# rigidPCB.net
KiCad netlist of a schematic drawn in Altium Designer
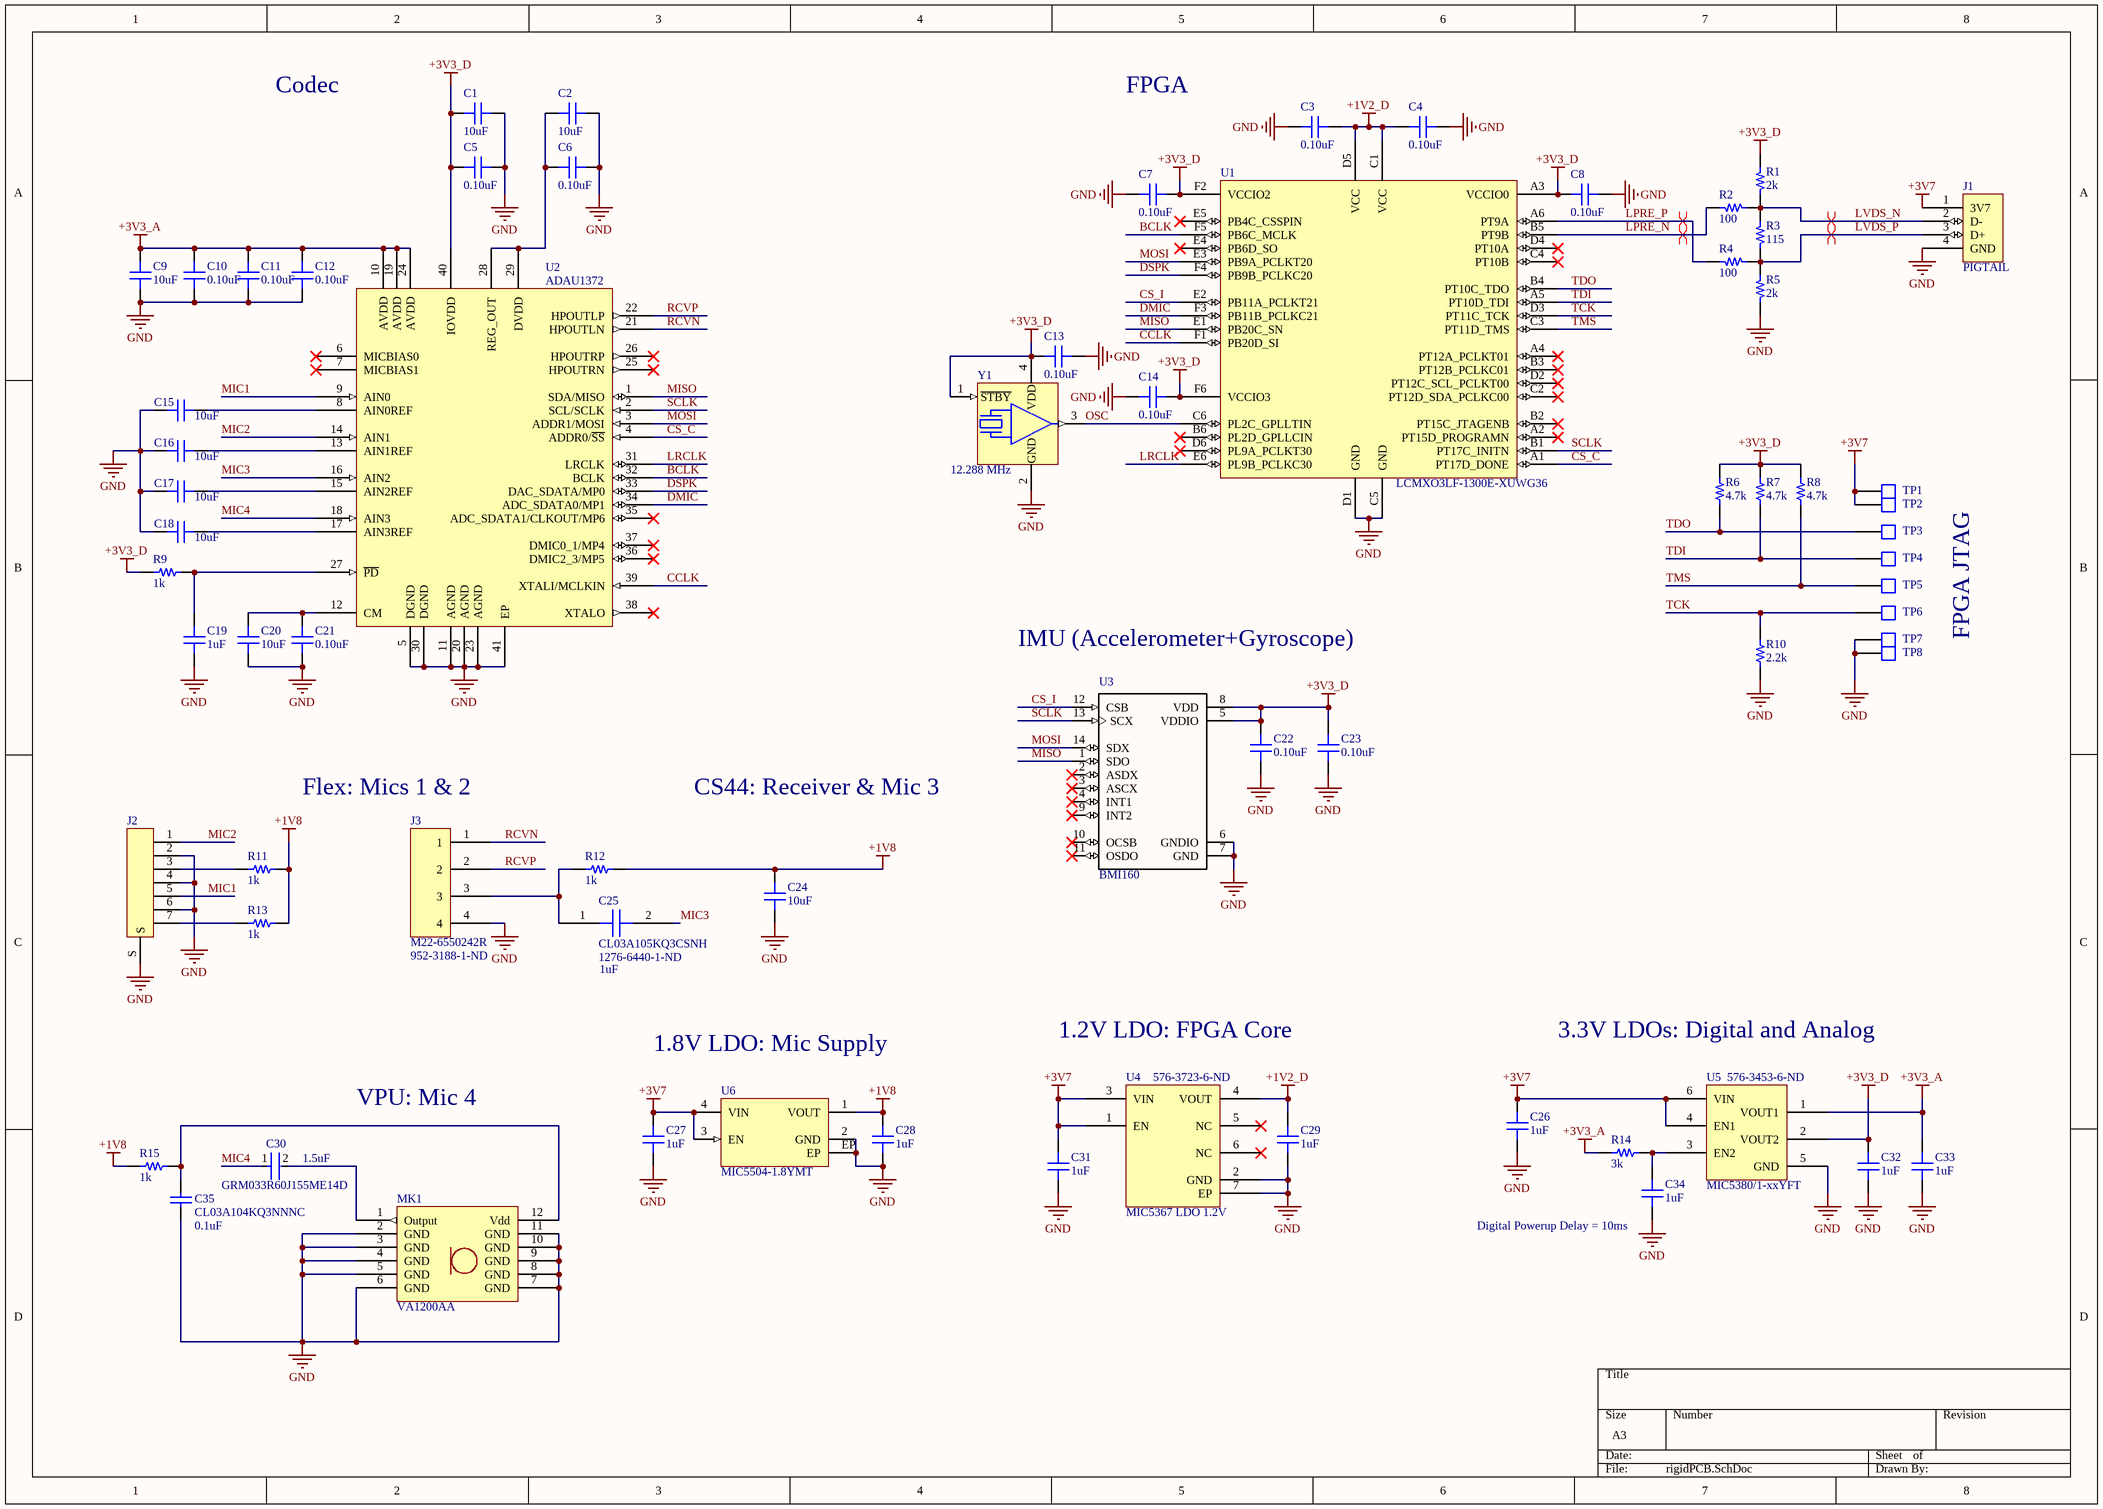
[diagram p0: rigidPCB.SchDoc]

(export (version "E")
  (design (tool "Eeschema 10.0.6"))
  (components
    (comp (ref "C1")
      (value "10uF")
      (footprint "CAP 0402/1005")
      (description "CAP CER 10UF 6.3V X5R 0402")
      (fields
        (field (name "PART NUMBER") "C1005X5R0J106M050BC")
        (field (name "MANUFACTURER") "TDK Corporation")
      )
      (libsource (lib "Celestial Library Database") (part "Capacitor"))
    )
    (comp (ref "C2")
      (value "10uF")
      (footprint "CAP 0402/1005")
      (description "CAP CER 10UF 6.3V X5R 0402")
      (fields
        (field (name "PART NUMBER") "C1005X5R0J106M050BC")
        (field (name "MANUFACTURER") "TDK Corporation")
      )
      (libsource (lib "Celestial Library Database") (part "Capacitor"))
    )
    (comp (ref "C3")
      (value "0.10uF")
      (footprint "CAP 0201/0603")
      (description "CAP CER 0.1UF 10V X5R 0201")
      (fields
        (field (name "PART NUMBER") "CL03A104KP3NNNC")
        (field (name "MANUFACTURER") "Samsung Electro-Mechanics America, Inc.")
      )
      (libsource (lib "Celestial Library Database") (part "Capacitor"))
    )
    (comp (ref "C4")
      (value "0.10uF")
      (footprint "CAP 0201/0603")
      (description "CAP CER 0.1UF 10V X5R 0201")
      (fields
        (field (name "PART NUMBER") "CL03A104KP3NNNC")
        (field (name "MANUFACTURER") "Samsung Electro-Mechanics America, Inc.")
      )
      (libsource (lib "Celestial Library Database") (part "Capacitor"))
    )
    (comp (ref "C5")
      (value "0.10uF")
      (footprint "CAP 0201/0603")
      (description "CAP CER 0.1UF 10V X5R 0201")
      (fields
        (field (name "PART NUMBER") "CL03A104KP3NNNC")
        (field (name "MANUFACTURER") "Samsung Electro-Mechanics America, Inc.")
      )
      (libsource (lib "Celestial Library Database") (part "Capacitor"))
    )
    (comp (ref "C6")
      (value "0.10uF")
      (footprint "CAP 0201/0603")
      (description "CAP CER 0.1UF 10V X5R 0201")
      (fields
        (field (name "PART NUMBER") "CL03A104KP3NNNC")
        (field (name "MANUFACTURER") "Samsung Electro-Mechanics America, Inc.")
      )
      (libsource (lib "Celestial Library Database") (part "Capacitor"))
    )
    (comp (ref "C7")
      (value "0.10uF")
      (footprint "CAP 0201/0603")
      (description "CAP CER 0.1UF 10V X5R 0201")
      (fields
        (field (name "PART NUMBER") "CL03A104KP3NNNC")
        (field (name "MANUFACTURER") "Samsung Electro-Mechanics America, Inc.")
      )
      (libsource (lib "Celestial Library Database") (part "Capacitor"))
    )
    (comp (ref "C8")
      (value "0.10uF")
      (footprint "CAP 0201/0603")
      (description "CAP CER 0.1UF 10V X5R 0201")
      (fields
        (field (name "PART NUMBER") "CL03A104KP3NNNC")
        (field (name "MANUFACTURER") "Samsung Electro-Mechanics America, Inc.")
      )
      (libsource (lib "Celestial Library Database") (part "Capacitor"))
    )
    (comp (ref "C9")
      (value "10uF")
      (footprint "CAP 0402/1005")
      (description "CAP CER 10UF 6.3V X5R 0402")
      (fields
        (field (name "PART NUMBER") "C1005X5R0J106M050BC")
        (field (name "MANUFACTURER") "TDK Corporation")
      )
      (libsource (lib "Celestial Library Database") (part "Capacitor"))
    )
    (comp (ref "C10")
      (value "0.10uF")
      (footprint "CAP 0201/0603")
      (description "CAP CER 0.1UF 10V X5R 0201")
      (fields
        (field (name "PART NUMBER") "CL03A104KP3NNNC")
        (field (name "MANUFACTURER") "Samsung Electro-Mechanics America, Inc.")
      )
      (libsource (lib "Celestial Library Database") (part "Capacitor"))
    )
    (comp (ref "C11")
      (value "0.10uF")
      (footprint "CAP 0201/0603")
      (description "CAP CER 0.1UF 10V X5R 0201")
      (fields
        (field (name "PART NUMBER") "CL03A104KP3NNNC")
        (field (name "MANUFACTURER") "Samsung Electro-Mechanics America, Inc.")
      )
      (libsource (lib "Celestial Library Database") (part "Capacitor"))
    )
    (comp (ref "C12")
      (value "0.10uF")
      (footprint "CAP 0201/0603")
      (description "CAP CER 0.1UF 10V X5R 0201")
      (fields
        (field (name "PART NUMBER") "CL03A104KP3NNNC")
        (field (name "MANUFACTURER") "Samsung Electro-Mechanics America, Inc.")
      )
      (libsource (lib "Celestial Library Database") (part "Capacitor"))
    )
    (comp (ref "C13")
      (value "0.10uF")
      (footprint "CAP 0201/0603")
      (description "CAP CER 0.1UF 10V X5R 0201")
      (fields
        (field (name "PART NUMBER") "CL03A104KP3NNNC")
        (field (name "MANUFACTURER") "Samsung Electro-Mechanics America, Inc.")
      )
      (libsource (lib "Celestial Library Database") (part "Capacitor"))
    )
    (comp (ref "C14")
      (value "0.10uF")
      (footprint "CAP 0201/0603")
      (description "CAP CER 0.1UF 10V X5R 0201")
      (fields
        (field (name "PART NUMBER") "CL03A104KP3NNNC")
        (field (name "MANUFACTURER") "Samsung Electro-Mechanics America, Inc.")
      )
      (libsource (lib "Celestial Library Database") (part "Capacitor"))
    )
    (comp (ref "C15")
      (value "10uF")
      (footprint "CAP 0402/1005")
      (description "CAP CER 10UF 6.3V X5R 0402")
      (fields
        (field (name "PART NUMBER") "C1005X5R0J106M050BC")
        (field (name "MANUFACTURER") "TDK Corporation")
      )
      (libsource (lib "Celestial Library Database") (part "Capacitor"))
    )
    (comp (ref "C16")
      (value "10uF")
      (footprint "CAP 0402/1005")
      (description "CAP CER 10UF 6.3V X5R 0402")
      (fields
        (field (name "PART NUMBER") "C1005X5R0J106M050BC")
        (field (name "MANUFACTURER") "TDK Corporation")
      )
      (libsource (lib "Celestial Library Database") (part "Capacitor"))
    )
    (comp (ref "C17")
      (value "10uF")
      (footprint "CAP 0402/1005")
      (description "CAP CER 10UF 6.3V X5R 0402")
      (fields
        (field (name "PART NUMBER") "C1005X5R0J106M050BC")
        (field (name "MANUFACTURER") "TDK Corporation")
      )
      (libsource (lib "Celestial Library Database") (part "Capacitor"))
    )
    (comp (ref "C18")
      (value "10uF")
      (footprint "CAP 0402/1005")
      (description "CAP CER 10UF 6.3V X5R 0402")
      (fields
        (field (name "PART NUMBER") "C1005X5R0J106M050BC")
        (field (name "MANUFACTURER") "TDK Corporation")
      )
      (libsource (lib "Celestial Library Database") (part "Capacitor"))
    )
    (comp (ref "C19")
      (value "1uF")
      (footprint "CAP 0201/0603")
      (description "CAP CER 1UF 6.3V X5R 0201")
      (fields (field (name "PART NUMBER") "02016D105MAT2A") (field (name "MANUFACTURER") "AVX Corporation"))
      (libsource (lib "Celestial Library Database") (part "Capacitor"))
    )
    (comp (ref "C20")
      (value "10uF")
      (footprint "CAP 0402/1005")
      (description "CAP CER 10UF 6.3V X5R 0402")
      (fields
        (field (name "PART NUMBER") "C1005X5R0J106M050BC")
        (field (name "MANUFACTURER") "TDK Corporation")
      )
      (libsource (lib "Celestial Library Database") (part "Capacitor"))
    )
    (comp (ref "C21")
      (value "0.10uF")
      (footprint "CAP 0201/0603")
      (description "CAP CER 0.1UF 10V X5R 0201")
      (fields
        (field (name "PART NUMBER") "CL03A104KP3NNNC")
        (field (name "MANUFACTURER") "Samsung Electro-Mechanics America, Inc.")
      )
      (libsource (lib "Celestial Library Database") (part "Capacitor"))
    )
    (comp (ref "C22")
      (value "0.10uF")
      (footprint "CAP 0201/0603")
      (description "CAP CER 0.1UF 10V X5R 0201")
      (fields
        (field (name "PART NUMBER") "CL03A104KP3NNNC")
        (field (name "MANUFACTURER") "Samsung Electro-Mechanics America, Inc.")
      )
      (libsource (lib "Celestial Library Database") (part "Capacitor"))
    )
    (comp (ref "C23")
      (value "0.10uF")
      (footprint "CAP 0201/0603")
      (description "CAP CER 0.1UF 10V X5R 0201")
      (fields
        (field (name "PART NUMBER") "CL03A104KP3NNNC")
        (field (name "MANUFACTURER") "Samsung Electro-Mechanics America, Inc.")
      )
      (libsource (lib "Celestial Library Database") (part "Capacitor"))
    )
    (comp (ref "C24")
      (value "10uF")
      (footprint "CAP 0402/1005")
      (description "CAP CER 10UF 6.3V X5R 0402")
      (fields
        (field (name "PART NUMBER") "C1005X5R0J106M050BC")
        (field (name "MANUFACTURER") "TDK Corporation")
      )
      (libsource (lib "Celestial Library Database") (part "Capacitor"))
    )
    (comp (ref "C25")
      (value "CL03A105KQ3CSNH")
      (footprint "CL03A105KQ3CSNH")
      (description "1 µF ±10% 6.3V Ceramic Capacitor X5R 0201 (0603 Metric)")
      (fields (field (name "SUPPLIER PART NUMBER 1") "1276-6440-1-ND"))
      (libsource (lib "OSP_DJB_Rigid") (part "CL03A105KQ3CSNH"))
    )
    (comp (ref "C26")
      (value "1uF")
      (footprint "CAP 0201/0603")
      (description "CAP CER 1UF 6.3V X5R 0201")
      (fields (field (name "PART NUMBER") "02016D105MAT2A") (field (name "MANUFACTURER") "AVX Corporation"))
      (libsource (lib "Celestial Library Database") (part "Capacitor"))
    )
    (comp (ref "C27")
      (value "1uF")
      (footprint "CAP 0201/0603")
      (description "CAP CER 1UF 6.3V X5R 0201")
      (fields (field (name "PART NUMBER") "02016D105MAT2A") (field (name "MANUFACTURER") "AVX Corporation"))
      (libsource (lib "Celestial Library Database") (part "Capacitor"))
    )
    (comp (ref "C28")
      (value "1uF")
      (footprint "CAP 0201/0603")
      (description "CAP CER 1UF 6.3V X5R 0201")
      (fields (field (name "PART NUMBER") "02016D105MAT2A") (field (name "MANUFACTURER") "AVX Corporation"))
      (libsource (lib "Celestial Library Database") (part "Capacitor"))
    )
    (comp (ref "C29")
      (value "1uF")
      (footprint "CAP 0201/0603")
      (description "CAP CER 1UF 6.3V X5R 0201")
      (fields (field (name "PART NUMBER") "02016D105MAT2A") (field (name "MANUFACTURER") "AVX Corporation"))
      (libsource (lib "Celestial Library Database") (part "Capacitor"))
    )
    (comp (ref "C30")
      (value "GRM033R60J155ME14D")
      (footprint "FP-GRM033-0_03-IPC_B")
      (description "Chip Multilayer Ceramic Capacitors for General Purpose, 0201, 1.5uF, X5R, 15%, 20%, 6.3V")
      (fields (field (name "TOLERANCE") "20%"))
      (libsource (lib "Altium Content Vault") (part "b4654b650e69147ec39a6b967a45e02"))
    )
    (comp (ref "C31")
      (value "1uF")
      (footprint "CAP 0201/0603")
      (description "CAP CER 1UF 6.3V X5R 0201")
      (fields (field (name "PART NUMBER") "02016D105MAT2A") (field (name "MANUFACTURER") "AVX Corporation"))
      (libsource (lib "Celestial Library Database") (part "Capacitor"))
    )
    (comp (ref "C32")
      (value "1uF")
      (footprint "CAP 0201/0603")
      (description "CAP CER 1UF 6.3V X5R 0201")
      (fields (field (name "PART NUMBER") "02016D105MAT2A") (field (name "MANUFACTURER") "AVX Corporation"))
      (libsource (lib "Celestial Library Database") (part "Capacitor"))
    )
    (comp (ref "C33")
      (value "1uF")
      (footprint "CAP 0201/0603")
      (description "CAP CER 1UF 6.3V X5R 0201")
      (fields (field (name "PART NUMBER") "02016D105MAT2A") (field (name "MANUFACTURER") "AVX Corporation"))
      (libsource (lib "Celestial Library Database") (part "Capacitor"))
    )
    (comp (ref "C34")
      (value "1uF")
      (footprint "CAP 0201/0603")
      (description "CAP CER 1UF 6.3V X5R 0201")
      (fields (field (name "PART NUMBER") "02016D105MAT2A") (field (name "MANUFACTURER") "AVX Corporation"))
      (libsource (lib "Celestial Library Database") (part "Capacitor"))
    )
    (comp (ref "C35")
      (value "CL03A104KQ3NNNC")
      (footprint "CAPC0603X33X15ML03T05")
      (fields (field (name "MANUFACTURER") "Samsung"))
      (libsource (lib "Altium Content Vault") (part "CAP"))
    )
    (comp (ref "J1")
      (value "PIGTAIL")
      (footprint "PIGTAIL")
      (libsource (lib "Mark_Library1") (part "PIGTAIL"))
    )
    (comp (ref "J2")
      (value "FFC")
      (footprint "HIROSE_FH58M-7S-0.25SHW-99")
      (description "Hirose FH58M-7S-0.25SHW(99) 7-pin Top+Bottom Contact FFC Connector")
      (libsource (lib "OSP_Symbols") (part "HIROSE_FH58M-7S-0.25SHW-99"))
    )
    (comp (ref "J3")
      (value "M22-6550242R")
      (footprint "M22-6550242R")
      (description "4 Position Receptacle Connector 0.079\" (2.00mm) Surface Mount, Right Angle Gold")
      (fields (field (name "SUPPLIER PART NUMBER 1") "952-3188-1-ND"))
      (libsource (lib "OSP_DJB_Rigid") (part "M22-6550242R"))
    )
    (comp (ref "MK1")
      (value "VA1200AA")
      (footprint "VA1200AA")
      (description "Bone Conductor Sensor Accelerometer")
      (libsource (lib "OSP_DJB_Rigid") (part "VA1200AA"))
    )
    (comp (ref "R1")
      (value "2k")
      (footprint "RES 0201/0603")
      (description "RES SMD 2K OHM 1% 1/20W 0201")
      (fields (field (name "PART NUMBER") "RC0201FR-072KL") (field (name "MANUFACTURER") "Yageo"))
      (libsource (lib "Celestial Library Database") (part "Resistor"))
    )
    (comp (ref "R2")
      (value "100")
      (footprint "RES 0201/0603")
      (description "RES SMD 100 OHM 1% 1/20W 0201")
      (fields
        (field (name "PART NUMBER") "RC0603F101CS")
        (field (name "MANUFACTURER") "Samsung Electro-Mechanics America, Inc.")
      )
      (libsource (lib "Celestial Library Database") (part "Resistor"))
    )
    (comp (ref "R3")
      (value "115")
      (footprint "RES 0201/0603")
      (description "RES SMD 115 OHM 1% 1/20W 0201")
      (fields (field (name "PART NUMBER") "RC0201FR-07115RL") (field (name "MANUFACTURER") "Yageo"))
      (libsource (lib "Celestial Library Database") (part "Resistor"))
    )
    (comp (ref "R4")
      (value "100")
      (footprint "RES 0201/0603")
      (description "RES SMD 100 OHM 1% 1/20W 0201")
      (fields
        (field (name "PART NUMBER") "RC0603F101CS")
        (field (name "MANUFACTURER") "Samsung Electro-Mechanics America, Inc.")
      )
      (libsource (lib "Celestial Library Database") (part "Resistor"))
    )
    (comp (ref "R5")
      (value "2k")
      (footprint "RES 0201/0603")
      (description "RES SMD 2K OHM 1% 1/20W 0201")
      (fields (field (name "PART NUMBER") "RC0201FR-072KL") (field (name "MANUFACTURER") "Yageo"))
      (libsource (lib "Celestial Library Database") (part "Resistor"))
    )
    (comp (ref "R6")
      (value "4.7k")
      (footprint "RES 0201/0603")
      (description "RES SMD 4.7K OHM 1% 1/20W 0201")
      (fields (field (name "PART NUMBER") "RC0201FR-074K7L") (field (name "MANUFACTURER") "Yageo"))
      (libsource (lib "Celestial Library Database") (part "Resistor"))
    )
    (comp (ref "R7")
      (value "4.7k")
      (footprint "RES 0201/0603")
      (description "RES SMD 4.7K OHM 1% 1/20W 0201")
      (fields (field (name "PART NUMBER") "RC0201FR-074K7L") (field (name "MANUFACTURER") "Yageo"))
      (libsource (lib "Celestial Library Database") (part "Resistor"))
    )
    (comp (ref "R8")
      (value "4.7k")
      (footprint "RES 0201/0603")
      (description "RES SMD 4.7K OHM 1% 1/20W 0201")
      (fields (field (name "PART NUMBER") "RC0201FR-074K7L") (field (name "MANUFACTURER") "Yageo"))
      (libsource (lib "Celestial Library Database") (part "Resistor"))
    )
    (comp (ref "R9")
      (value "1k")
      (footprint "RES 0201/0603")
      (description "RES SMD 1K OHM 5% 1/20W 0201")
      (fields (field (name "PART NUMBER") "RC0201JR-071KL") (field (name "MANUFACTURER") "Yageo"))
      (libsource (lib "Celestial Library Database") (part "Resistor"))
    )
    (comp (ref "R10")
      (value "2.2k")
      (footprint "RES 0201/0603")
      (description "RES SMD 2.2K OHM 1% 1/20W 0201")
      (fields
        (field (name "PART NUMBER") "RC0603F222CS")
        (field (name "MANUFACTURER") "Samsung Electro-Mechanics America, Inc.")
      )
      (libsource (lib "Celestial Library Database") (part "Resistor"))
    )
    (comp (ref "R11")
      (value "1k")
      (footprint "RES 0201/0603")
      (description "RES SMD 1K OHM 5% 1/20W 0201")
      (fields (field (name "PART NUMBER") "RC0201JR-071KL") (field (name "MANUFACTURER") "Yageo"))
      (libsource (lib "Celestial Library Database") (part "Resistor"))
    )
    (comp (ref "R12")
      (value "1k")
      (footprint "RES 0201/0603")
      (description "RES SMD 1K OHM 5% 1/20W 0201")
      (fields (field (name "PART NUMBER") "RC0201JR-071KL") (field (name "MANUFACTURER") "Yageo"))
      (libsource (lib "Celestial Library Database") (part "Resistor"))
    )
    (comp (ref "R13")
      (value "1k")
      (footprint "RES 0201/0603")
      (description "RES SMD 1K OHM 5% 1/20W 0201")
      (fields (field (name "PART NUMBER") "RC0201JR-071KL") (field (name "MANUFACTURER") "Yageo"))
      (libsource (lib "Celestial Library Database") (part "Resistor"))
    )
    (comp (ref "R14")
      (value "3k")
      (footprint "RES 0201/0603")
      (description "RES SMD 3K OHM 1% 1/20W 0201")
      (fields (field (name "PART NUMBER") "RC0201FR-073KL") (field (name "MANUFACTURER") "Yageo"))
      (libsource (lib "Celestial Library Database") (part "Resistor"))
    )
    (comp (ref "R15")
      (value "1k")
      (footprint "RES 0201/0603")
      (description "RES SMD 1K OHM 5% 1/20W 0201")
      (fields (field (name "PART NUMBER") "RC0201JR-071KL") (field (name "MANUFACTURER") "Yageo"))
      (libsource (lib "Celestial Library Database") (part "Resistor"))
    )
    (comp (ref "TP1")
      (value "TP_SMD_DJB")
      (footprint "TP_SMD_DJB")
      (description "Digital Jellybean Style SMD Test Point")
      (libsource (lib "OSP_Symbols") (part "TP_SMD_DJB"))
    )
    (comp (ref "TP2")
      (value "TP_SMD_DJB")
      (footprint "TP_SMD_DJB")
      (description "Digital Jellybean Style SMD Test Point")
      (libsource (lib "OSP_Symbols") (part "TP_SMD_DJB"))
    )
    (comp (ref "TP3")
      (value "TP_SMD_DJB")
      (footprint "TP_SMD_DJB")
      (description "Digital Jellybean Style SMD Test Point")
      (libsource (lib "OSP_Symbols") (part "TP_SMD_DJB"))
    )
    (comp (ref "TP4")
      (value "TP_SMD_DJB")
      (footprint "TP_SMD_DJB")
      (description "Digital Jellybean Style SMD Test Point")
      (libsource (lib "OSP_Symbols") (part "TP_SMD_DJB"))
    )
    (comp (ref "TP5")
      (value "TP_SMD_DJB")
      (footprint "TP_SMD_DJB")
      (description "Digital Jellybean Style SMD Test Point")
      (libsource (lib "OSP_Symbols") (part "TP_SMD_DJB"))
    )
    (comp (ref "TP6")
      (value "TP_SMD_DJB")
      (footprint "TP_SMD_DJB")
      (description "Digital Jellybean Style SMD Test Point")
      (libsource (lib "OSP_Symbols") (part "TP_SMD_DJB"))
    )
    (comp (ref "TP7")
      (value "TP_SMD_DJB")
      (footprint "TP_SMD_DJB")
      (description "Digital Jellybean Style SMD Test Point")
      (libsource (lib "OSP_Symbols") (part "TP_SMD_DJB"))
    )
    (comp (ref "TP8")
      (value "TP_SMD_DJB")
      (footprint "TP_SMD_DJB")
      (description "Digital Jellybean Style SMD Test Point")
      (libsource (lib "OSP_Symbols") (part "TP_SMD_DJB"))
    )
    (comp (ref "U1")
      (value "LCMXO3LF-1300E-XUWG36")
      (footprint "BGA36_WLCS_25x25_MachXO3")
      (description "Lattice MachXO3 36-ball 2.5x2.5mm FPGA")
      (libsource (lib "OSP_Symbols") (part "LCMXO3LF-1300E-XUWG36"))
    )
    (comp (ref "U2")
      (value "ADAU1372")
      (footprint "QFN40_LFCSP_WQ_6mmx6mm")
      (description "Analog Devices CODEC")
      (libsource (lib "Mark_Library1") (part "ADAU1372"))
    )
    (comp (ref "U3")
      (value "BMI160")
      (footprint "LGA14R50P5X4_300X250X83")
      (description "BMI160 2.5 x 3 mm Tiaxial Accelerometer / Gyroscope Inertial Measurement Unit")
      (fields (field (name "MF") "Bosch"))
      (libsource (lib "Mark_Library1") (part "BMI160_1"))
    )
    (comp (ref "U4")
      (value "MIC5367 LDO 1.2V")
      (footprint "LDO 1.2V")
      (fields (field (name "SUPPLIER PART NUMBER 1") "576-3723-6-ND"))
      (libsource (lib "Mark_Library1") (part "MIC5367 LDO 1.2V"))
    )
    (comp (ref "U5")
      (value "MIC5380/1-xxYFT")
      (footprint "06L FCSTSLP")
      (description "LDO 2fixed Outputs")
      (fields (field (name "SUPPLIER PART NUMBER 1") "576-3453-6-ND"))
      (libsource (lib "Mark_Library1") (part "MIC5380/1-xxYFT"))
    )
    (comp (ref "U6")
      (value "MIC5504-1.8YMT")
      (footprint "MICREL_DFN4")
      (description "Micrel MIC5504-1.8YMT 1.8V 300mA LDO")
      (libsource (lib "OSP_Symbols") (part "MICREL_MIC5504-1.8YMT"))
    )
    (comp (ref "Y1")
      (value "12.288 MHz")
      (footprint "OSC_2.5x2.0mm")
      (description "Microchip 12.288 MHz SMD MEMS Oscillator")
      (libsource (lib "OSP_Symbols") (part "MC_DSC1033DI2-012.2880"))
    )
  )
  (nets
    (net (code "1") (name "+1V2_D") (class "Default")
      (node (ref "C29") (pin "2") (pinfunction "2_2") (pintype "passive"))
      (node (ref "C3") (pin "1") (pinfunction "1_1") (pintype "passive"))
      (node (ref "C4") (pin "2") (pinfunction "2_2") (pintype "passive"))
      (node (ref "U1") (pin "C1") (pinfunction "VCC_C1") (pintype "power_in"))
      (node (ref "U1") (pin "D5") (pinfunction "VCC_D5") (pintype "power_in"))
      (node (ref "U4") (pin "4") (pinfunction "VOUT_4") (pintype "passive"))
    )
    (net (code "2") (name "+1V8") (class "Default")
      (node (ref "C24") (pin "2") (pinfunction "2_2") (pintype "passive"))
      (node (ref "C28") (pin "2") (pinfunction "2_2") (pintype "passive"))
      (node (ref "R11") (pin "2") (pinfunction "2_2") (pintype "passive"))
      (node (ref "R12") (pin "2") (pinfunction "2_2") (pintype "passive"))
      (node (ref "R13") (pin "2") (pinfunction "2_2") (pintype "passive"))
      (node (ref "R15") (pin "1") (pinfunction "1_1") (pintype "passive"))
      (node (ref "U6") (pin "1") (pinfunction "VOUT_1") (pintype "power_in"))
    )
    (net (code "3") (name "+3V3_A") (class "Default")
      (node (ref "C10") (pin "2") (pinfunction "2_2") (pintype "passive"))
      (node (ref "C11") (pin "2") (pinfunction "2_2") (pintype "passive"))
      (node (ref "C12") (pin "2") (pinfunction "2_2") (pintype "passive"))
      (node (ref "C33") (pin "2") (pinfunction "2_2") (pintype "passive"))
      (node (ref "C9") (pin "1") (pinfunction "1_1") (pintype "passive"))
      (node (ref "R14") (pin "1") (pinfunction "1_1") (pintype "passive"))
      (node (ref "U2") (pin "10") (pinfunction "AVDD_10") (pintype "power_in"))
      (node (ref "U2") (pin "19") (pinfunction "AVDD_19") (pintype "power_in"))
      (node (ref "U2") (pin "24") (pinfunction "AVDD_24") (pintype "power_in"))
      (node (ref "U5") (pin "1") (pinfunction "VOUT1_1") (pintype "passive"))
    )
    (net (code "4") (name "+3V3_D") (class "Default")
      (node (ref "C1") (pin "2") (pinfunction "2_2") (pintype "passive"))
      (node (ref "C13") (pin "2") (pinfunction "2_2") (pintype "passive"))
      (node (ref "C14") (pin "1") (pinfunction "1_1") (pintype "passive"))
      (node (ref "C22") (pin "2") (pinfunction "2_2") (pintype "passive"))
      (node (ref "C23") (pin "2") (pinfunction "2_2") (pintype "passive"))
      (node (ref "C32") (pin "2") (pinfunction "2_2") (pintype "passive"))
      (node (ref "C5") (pin "1") (pinfunction "1_1") (pintype "passive"))
      (node (ref "C7") (pin "1") (pinfunction "1_1") (pintype "passive"))
      (node (ref "C8") (pin "2") (pinfunction "2_2") (pintype "passive"))
      (node (ref "R1") (pin "2") (pinfunction "2_2") (pintype "passive"))
      (node (ref "R6") (pin "2") (pinfunction "2_2") (pintype "passive"))
      (node (ref "R7") (pin "2") (pinfunction "2_2") (pintype "passive"))
      (node (ref "R8") (pin "2") (pinfunction "2_2") (pintype "passive"))
      (node (ref "R9") (pin "1") (pinfunction "1_1") (pintype "passive"))
      (node (ref "U1") (pin "A3") (pinfunction "VCCIO0_A3") (pintype "power_in"))
      (node (ref "U1") (pin "F2") (pinfunction "VCCIO2_F2") (pintype "power_in"))
      (node (ref "U1") (pin "F6") (pinfunction "VCCIO3_F6") (pintype "power_in"))
      (node (ref "U2") (pin "40") (pinfunction "IOVDD_40") (pintype "power_in"))
      (node (ref "U3") (pin "5") (pinfunction "VDDIO_5") (pintype "power_in"))
      (node (ref "U3") (pin "8") (pinfunction "VDD_8") (pintype "power_in"))
      (node (ref "U5") (pin "2") (pinfunction "VOUT2_2") (pintype "passive"))
      (node (ref "Y1") (pin "1") (pinfunction "~{STBY}_1") (pintype "input"))
      (node (ref "Y1") (pin "4") (pinfunction "VDD_4") (pintype "power_in"))
    )
    (net (code "5") (name "+3V7") (class "Default")
      (node (ref "C26") (pin "2") (pinfunction "2_2") (pintype "passive"))
      (node (ref "C27") (pin "2") (pinfunction "2_2") (pintype "passive"))
      (node (ref "C31") (pin "2") (pinfunction "2_2") (pintype "passive"))
      (node (ref "J1") (pin "1") (pinfunction "3V7_1") (pintype "power_in"))
      (node (ref "TP1") (pin "1") (pintype "passive"))
      (node (ref "TP2") (pin "1") (pintype "passive"))
      (node (ref "U4") (pin "1") (pinfunction "EN_1") (pintype "passive"))
      (node (ref "U4") (pin "3") (pinfunction "VIN_3") (pintype "passive"))
      (node (ref "U5") (pin "4") (pinfunction "EN1_4") (pintype "passive"))
      (node (ref "U5") (pin "6") (pinfunction "VIN_6") (pintype "passive"))
      (node (ref "U6") (pin "3") (pinfunction "EN_3") (pintype "input"))
      (node (ref "U6") (pin "4") (pinfunction "VIN_4") (pintype "power_in"))
    )
    (net (code "6") (name "/BCLK") (class "Default")
      (node (ref "U1") (pin "F5") (pinfunction "PB6C_MCLK_F5") (pintype "bidirectional"))
      (node (ref "U2") (pin "32") (pinfunction "BCLK_32") (pintype "bidirectional"))
    )
    (net (code "7") (name "/CCLK") (class "Default")
      (node (ref "U1") (pin "F1") (pinfunction "PB20D_SI_F1") (pintype "bidirectional"))
      (node (ref "U2") (pin "39") (pinfunction "XTALI/MCLKIN_39") (pintype "input"))
    )
    (net (code "8") (name "/CS_C") (class "Default")
      (node (ref "U1") (pin "A1") (pinfunction "PT17D_DONE_A1") (pintype "bidirectional"))
      (node (ref "U2") (pin "4") (pinfunction "ADDR0/~{SS}_4") (pintype "input"))
    )
    (net (code "9") (name "/CS_I") (class "Default")
      (node (ref "U1") (pin "E2") (pinfunction "PB11A_PCLKT21_E2") (pintype "bidirectional"))
      (node (ref "U3") (pin "12") (pinfunction "CSB_12") (pintype "input"))
    )
    (net (code "10") (name "/DMIC") (class "Default")
      (node (ref "U1") (pin "F3") (pinfunction "PB11B_PCLKC21_F3") (pintype "bidirectional"))
      (node (ref "U2") (pin "34") (pinfunction "ADC_SDATA0/MP1_34") (pintype "bidirectional"))
    )
    (net (code "11") (name "/DSPK") (class "Default")
      (node (ref "U1") (pin "F4") (pinfunction "PB9B_PCLKC20_F4") (pintype "bidirectional"))
      (node (ref "U2") (pin "33") (pinfunction "DAC_SDATA/MP0_33") (pintype "bidirectional"))
    )
    (net (code "12") (name "/LPRE_N") (class "Default")
      (node (ref "R2") (pin "2") (pinfunction "2_2") (pintype "passive"))
      (node (ref "U1") (pin "B5") (pinfunction "PT9B_B5") (pintype "bidirectional"))
    )
    (net (code "13") (name "/LPRE_P") (class "Default")
      (node (ref "R4") (pin "2") (pinfunction "2_2") (pintype "passive"))
      (node (ref "U1") (pin "A6") (pinfunction "PT9A_A6") (pintype "bidirectional"))
    )
    (net (code "14") (name "/LRCLK") (class "Default")
      (node (ref "U1") (pin "E6") (pinfunction "PL9B_PCLKC30_E6") (pintype "bidirectional"))
      (node (ref "U2") (pin "31") (pinfunction "LRCLK_31") (pintype "bidirectional"))
    )
    (net (code "15") (name "/LVDS_N") (class "Default")
      (node (ref "J1") (pin "2") (pinfunction "D-_2") (pintype "bidirectional"))
      (node (ref "R1") (pin "1") (pinfunction "1_1") (pintype "passive"))
      (node (ref "R2") (pin "1") (pinfunction "1_1") (pintype "passive"))
      (node (ref "R3") (pin "2") (pinfunction "2_2") (pintype "passive"))
    )
    (net (code "16") (name "/LVDS_P") (class "Default")
      (node (ref "J1") (pin "3") (pinfunction "D+_3") (pintype "bidirectional"))
      (node (ref "R3") (pin "1") (pinfunction "1_1") (pintype "passive"))
      (node (ref "R4") (pin "1") (pinfunction "1_1") (pintype "passive"))
      (node (ref "R5") (pin "2") (pinfunction "2_2") (pintype "passive"))
    )
    (net (code "17") (name "/MIC1") (class "Default")
      (node (ref "J2") (pin "5") (pintype "passive"))
      (node (ref "U2") (pin "9") (pinfunction "AIN0_9") (pintype "input"))
    )
    (net (code "18") (name "/MIC2") (class "Default")
      (node (ref "J2") (pin "1") (pintype "passive"))
      (node (ref "U2") (pin "14") (pinfunction "AIN1_14") (pintype "input"))
    )
    (net (code "19") (name "/MIC3") (class "Default")
      (node (ref "C25") (pin "2") (pinfunction "2_2") (pintype "passive"))
      (node (ref "U2") (pin "16") (pinfunction "AIN2_16") (pintype "input"))
    )
    (net (code "20") (name "/MIC4") (class "Default")
      (node (ref "C30") (pin "1") (pinfunction "1_1") (pintype "passive"))
      (node (ref "U2") (pin "18") (pinfunction "AIN3_18") (pintype "input"))
    )
    (net (code "21") (name "/MISO") (class "Default")
      (node (ref "U1") (pin "E1") (pinfunction "PB20C_SN_E1") (pintype "bidirectional"))
      (node (ref "U2") (pin "1") (pinfunction "SDA/MISO_1") (pintype "bidirectional"))
      (node (ref "U3") (pin "1") (pinfunction "SDO_1") (pintype "bidirectional"))
    )
    (net (code "22") (name "/MOSI") (class "Default")
      (node (ref "U1") (pin "E3") (pinfunction "PB9A_PCLKT20_E3") (pintype "bidirectional"))
      (node (ref "U2") (pin "3") (pinfunction "ADDR1/MOSI_3") (pintype "input"))
      (node (ref "U3") (pin "14") (pinfunction "SDX_14") (pintype "bidirectional"))
    )
    (net (code "23") (name "/OSC") (class "Default")
      (node (ref "U1") (pin "C6") (pinfunction "PL2C_GPLLTIN_C6") (pintype "bidirectional"))
      (node (ref "Y1") (pin "3") (pinfunction "OUT_3") (pintype "output"))
    )
    (net (code "24") (name "/RCVN") (class "Default")
      (node (ref "J3") (pin "1") (pinfunction "1_1") (pintype "passive"))
      (node (ref "U2") (pin "21") (pinfunction "HPOUTLN_21") (pintype "output"))
    )
    (net (code "25") (name "/RCVP") (class "Default")
      (node (ref "J3") (pin "2") (pinfunction "2_2") (pintype "passive"))
      (node (ref "U2") (pin "22") (pinfunction "HPOUTLP_22") (pintype "output"))
    )
    (net (code "26") (name "/SCLK") (class "Default")
      (node (ref "U1") (pin "B1") (pinfunction "PT17C_INITN_B1") (pintype "bidirectional"))
      (node (ref "U2") (pin "2") (pinfunction "SCL/SCLK_2") (pintype "input"))
      (node (ref "U3") (pin "13") (pinfunction "SCX_13") (pintype "input"))
    )
    (net (code "27") (name "/TCK") (class "Default")
      (node (ref "R10") (pin "2") (pinfunction "2_2") (pintype "passive"))
      (node (ref "TP6") (pin "1") (pintype "passive"))
      (node (ref "U1") (pin "D3") (pinfunction "PT11C_TCK_D3") (pintype "bidirectional"))
    )
    (net (code "28") (name "/TDI") (class "Default")
      (node (ref "R7") (pin "1") (pinfunction "1_1") (pintype "passive"))
      (node (ref "TP4") (pin "1") (pintype "passive"))
      (node (ref "U1") (pin "A5") (pinfunction "PT10D_TDI_A5") (pintype "bidirectional"))
    )
    (net (code "29") (name "/TDO") (class "Default")
      (node (ref "R6") (pin "1") (pinfunction "1_1") (pintype "passive"))
      (node (ref "TP3") (pin "1") (pintype "passive"))
      (node (ref "U1") (pin "B4") (pinfunction "PT10C_TDO_B4") (pintype "bidirectional"))
    )
    (net (code "30") (name "/TMS") (class "Default")
      (node (ref "R8") (pin "1") (pinfunction "1_1") (pintype "passive"))
      (node (ref "TP5") (pin "1") (pintype "passive"))
      (node (ref "U1") (pin "C3") (pinfunction "PT11D_TMS_C3") (pintype "bidirectional"))
    )
    (net (code "31") (name "GND") (class "Default")
      (node (ref "C1") (pin "1") (pinfunction "1_1") (pintype "passive"))
      (node (ref "C10") (pin "1") (pinfunction "1_1") (pintype "passive"))
      (node (ref "C11") (pin "1") (pinfunction "1_1") (pintype "passive"))
      (node (ref "C12") (pin "1") (pinfunction "1_1") (pintype "passive"))
      (node (ref "C13") (pin "1") (pinfunction "1_1") (pintype "passive"))
      (node (ref "C14") (pin "2") (pinfunction "2_2") (pintype "passive"))
      (node (ref "C15") (pin "2") (pinfunction "2_2") (pintype "passive"))
      (node (ref "C16") (pin "2") (pinfunction "2_2") (pintype "passive"))
      (node (ref "C17") (pin "2") (pinfunction "2_2") (pintype "passive"))
      (node (ref "C18") (pin "2") (pinfunction "2_2") (pintype "passive"))
      (node (ref "C19") (pin "1") (pinfunction "1_1") (pintype "passive"))
      (node (ref "C2") (pin "1") (pinfunction "1_1") (pintype "passive"))
      (node (ref "C20") (pin "2") (pinfunction "2_2") (pintype "passive"))
      (node (ref "C21") (pin "1") (pinfunction "1_1") (pintype "passive"))
      (node (ref "C22") (pin "1") (pinfunction "1_1") (pintype "passive"))
      (node (ref "C23") (pin "1") (pinfunction "1_1") (pintype "passive"))
      (node (ref "C24") (pin "1") (pinfunction "1_1") (pintype "passive"))
      (node (ref "C26") (pin "1") (pinfunction "1_1") (pintype "passive"))
      (node (ref "C27") (pin "1") (pinfunction "1_1") (pintype "passive"))
      (node (ref "C28") (pin "1") (pinfunction "1_1") (pintype "passive"))
      (node (ref "C29") (pin "1") (pinfunction "1_1") (pintype "passive"))
      (node (ref "C3") (pin "2") (pinfunction "2_2") (pintype "passive"))
      (node (ref "C31") (pin "1") (pinfunction "1_1") (pintype "passive"))
      (node (ref "C32") (pin "1") (pinfunction "1_1") (pintype "passive"))
      (node (ref "C33") (pin "1") (pinfunction "1_1") (pintype "passive"))
      (node (ref "C34") (pin "1") (pinfunction "1_1") (pintype "passive"))
      (node (ref "C35") (pin "1") (pinfunction "1_1") (pintype "passive"))
      (node (ref "C4") (pin "1") (pinfunction "1_1") (pintype "passive"))
      (node (ref "C5") (pin "2") (pinfunction "2_2") (pintype "passive"))
      (node (ref "C6") (pin "2") (pinfunction "2_2") (pintype "passive"))
      (node (ref "C7") (pin "2") (pinfunction "2_2") (pintype "passive"))
      (node (ref "C8") (pin "1") (pinfunction "1_1") (pintype "passive"))
      (node (ref "C9") (pin "2") (pinfunction "2_2") (pintype "passive"))
      (node (ref "J1") (pin "4") (pinfunction "GND_4") (pintype "power_in"))
      (node (ref "J2") (pin "2") (pintype "passive"))
      (node (ref "J2") (pin "4") (pintype "passive"))
      (node (ref "J2") (pin "6") (pintype "passive"))
      (node (ref "J2") (pin "S") (pinfunction "S_S") (pintype "power_in"))
      (node (ref "J3") (pin "4") (pinfunction "4_4") (pintype "passive"))
      (node (ref "MK1") (pin "10") (pinfunction "GND_10") (pintype "power_in"))
      (node (ref "MK1") (pin "11") (pinfunction "GND_11") (pintype "power_in"))
      (node (ref "MK1") (pin "2") (pinfunction "GND_2") (pintype "power_in"))
      (node (ref "MK1") (pin "3") (pinfunction "GND_3") (pintype "power_in"))
      (node (ref "MK1") (pin "4") (pinfunction "GND_4") (pintype "power_in"))
      (node (ref "MK1") (pin "5") (pinfunction "GND_5") (pintype "power_in"))
      (node (ref "MK1") (pin "6") (pinfunction "GND_6") (pintype "power_in"))
      (node (ref "MK1") (pin "7") (pinfunction "GND_7") (pintype "power_in"))
      (node (ref "MK1") (pin "8") (pinfunction "GND_8") (pintype "power_in"))
      (node (ref "MK1") (pin "9") (pinfunction "GND_9") (pintype "power_in"))
      (node (ref "R10") (pin "1") (pinfunction "1_1") (pintype "passive"))
      (node (ref "R5") (pin "1") (pinfunction "1_1") (pintype "passive"))
      (node (ref "TP7") (pin "1") (pintype "passive"))
      (node (ref "TP8") (pin "1") (pintype "passive"))
      (node (ref "U1") (pin "C5") (pinfunction "GND_C5") (pintype "power_in"))
      (node (ref "U1") (pin "D1") (pinfunction "GND_D1") (pintype "power_in"))
      (node (ref "U2") (pin "11") (pinfunction "AGND_11") (pintype "power_in"))
      (node (ref "U2") (pin "20") (pinfunction "AGND_20") (pintype "power_in"))
      (node (ref "U2") (pin "23") (pinfunction "AGND_23") (pintype "power_in"))
      (node (ref "U2") (pin "30") (pinfunction "DGND_30") (pintype "power_in"))
      (node (ref "U2") (pin "41") (pinfunction "EP_41") (pintype "power_in"))
      (node (ref "U2") (pin "5") (pinfunction "DGND_5") (pintype "power_in"))
      (node (ref "U3") (pin "6") (pinfunction "GNDIO_6") (pintype "power_in"))
      (node (ref "U3") (pin "7") (pinfunction "GND_7") (pintype "power_in"))
      (node (ref "U4") (pin "2") (pinfunction "GND_2") (pintype "passive"))
      (node (ref "U4") (pin "7") (pinfunction "EP_7") (pintype "passive"))
      (node (ref "U5") (pin "5") (pinfunction "GND_5") (pintype "passive"))
      (node (ref "U6") (pin "2") (pinfunction "GND_2") (pintype "power_in"))
      (node (ref "U6") (pin "EP") (pinfunction "EP_EP") (pintype "power_in"))
      (node (ref "Y1") (pin "2") (pinfunction "GND_2") (pintype "power_in"))
    )
    (net (code "32") (name "Net-(C25-Pad1)") (class "Default")
      (node (ref "C25") (pin "1") (pinfunction "1_1") (pintype "passive"))
      (node (ref "J3") (pin "3") (pinfunction "3_3") (pintype "passive"))
      (node (ref "R12") (pin "1") (pinfunction "1_1") (pintype "passive"))
    )
    (net (code "33") (name "Net-(J2-Pad3)") (class "Default")
      (node (ref "J2") (pin "3") (pintype "passive"))
      (node (ref "R11") (pin "1") (pinfunction "1_1") (pintype "passive"))
    )
    (net (code "34") (name "Net-(J2-Pad7)") (class "Default")
      (node (ref "J2") (pin "7") (pintype "passive"))
      (node (ref "R13") (pin "1") (pinfunction "1_1") (pintype "passive"))
    )
    (net (code "35") (name "Net-(MK1-Output)") (class "Default")
      (node (ref "C30") (pin "2") (pinfunction "2_2") (pintype "passive"))
      (node (ref "MK1") (pin "1") (pinfunction "Output_1") (pintype "output"))
    )
    (net (code "36") (name "Net-(MK1-Vdd)") (class "Default")
      (node (ref "C35") (pin "2") (pinfunction "2_2") (pintype "passive"))
      (node (ref "MK1") (pin "12") (pinfunction "Vdd_12") (pintype "power_in"))
      (node (ref "R15") (pin "2") (pinfunction "2_2") (pintype "passive"))
    )
    (net (code "37") (name "Net-(U2-AIN0REF)") (class "Default")
      (node (ref "C15") (pin "1") (pinfunction "1_1") (pintype "passive"))
      (node (ref "U2") (pin "8") (pinfunction "AIN0REF_8") (pintype "passive"))
    )
    (net (code "38") (name "Net-(U2-AIN1REF)") (class "Default")
      (node (ref "C16") (pin "1") (pinfunction "1_1") (pintype "passive"))
      (node (ref "U2") (pin "13") (pinfunction "AIN1REF_13") (pintype "passive"))
    )
    (net (code "39") (name "Net-(U2-AIN2REF)") (class "Default")
      (node (ref "C17") (pin "1") (pinfunction "1_1") (pintype "passive"))
      (node (ref "U2") (pin "15") (pinfunction "AIN2REF_15") (pintype "passive"))
    )
    (net (code "40") (name "Net-(U2-AIN3REF)") (class "Default")
      (node (ref "C18") (pin "1") (pinfunction "1_1") (pintype "passive"))
      (node (ref "U2") (pin "17") (pinfunction "AIN3REF_17") (pintype "passive"))
    )
    (net (code "41") (name "Net-(U2-CM)") (class "Default")
      (node (ref "C20") (pin "1") (pinfunction "1_1") (pintype "passive"))
      (node (ref "C21") (pin "2") (pinfunction "2_2") (pintype "passive"))
      (node (ref "U2") (pin "12") (pinfunction "CM_12") (pintype "power_in"))
    )
    (net (code "42") (name "Net-(U2-DVDD)") (class "Default")
      (node (ref "C2") (pin "2") (pinfunction "2_2") (pintype "passive"))
      (node (ref "C6") (pin "1") (pinfunction "1_1") (pintype "passive"))
      (node (ref "U2") (pin "28") (pinfunction "REG_OUT_28") (pintype "power_in"))
      (node (ref "U2") (pin "29") (pinfunction "DVDD_29") (pintype "power_in"))
    )
    (net (code "43") (name "Net-(U2-~{PD})") (class "Default")
      (node (ref "C19") (pin "2") (pinfunction "2_2") (pintype "passive"))
      (node (ref "R9") (pin "2") (pinfunction "2_2") (pintype "passive"))
      (node (ref "U2") (pin "27") (pinfunction "~{PD}_27") (pintype "input"))
    )
    (net (code "44") (name "Net-(U5-EN2)") (class "Default")
      (node (ref "C34") (pin "2") (pinfunction "2_2") (pintype "passive"))
      (node (ref "R14") (pin "2") (pinfunction "2_2") (pintype "passive"))
      (node (ref "U5") (pin "3") (pinfunction "EN2_3") (pintype "passive"))
    )
    (net (code "45") (name "unconnected-(U1-PB4C_CSSPIN-PadE5)") (class "Default")
      (node (ref "U1") (pin "E5") (pinfunction "PB4C_CSSPIN_E5") (pintype "bidirectional+no_connect"))
    )
    (net (code "46") (name "unconnected-(U1-PB6D_SO-PadE4)") (class "Default")
      (node (ref "U1") (pin "E4") (pinfunction "PB6D_SO_E4") (pintype "bidirectional+no_connect"))
    )
    (net (code "47") (name "unconnected-(U1-PL2D_GPLLCIN-PadB6)") (class "Default")
      (node (ref "U1") (pin "B6") (pinfunction "PL2D_GPLLCIN_B6") (pintype "bidirectional+no_connect"))
    )
    (net (code "48") (name "unconnected-(U1-PL9A_PCLKT30-PadD6)") (class "Default")
      (node (ref "U1") (pin "D6") (pinfunction "PL9A_PCLKT30_D6") (pintype "bidirectional+no_connect"))
    )
    (net (code "49") (name "unconnected-(U1-PT10A-PadD4)") (class "Default")
      (node (ref "U1") (pin "D4") (pinfunction "PT10A_D4") (pintype "bidirectional+no_connect"))
    )
    (net (code "50") (name "unconnected-(U1-PT10B-PadC4)") (class "Default")
      (node (ref "U1") (pin "C4") (pinfunction "PT10B_C4") (pintype "bidirectional+no_connect"))
    )
    (net (code "51") (name "unconnected-(U1-PT12A_PCLKT01-PadA4)") (class "Default")
      (node (ref "U1") (pin "A4") (pinfunction "PT12A_PCLKT01_A4") (pintype "bidirectional+no_connect"))
    )
    (net (code "52") (name "unconnected-(U1-PT12B_PCLKC01-PadB3)") (class "Default")
      (node (ref "U1") (pin "B3") (pinfunction "PT12B_PCLKC01_B3") (pintype "bidirectional+no_connect"))
    )
    (net (code "53") (name "unconnected-(U1-PT12C_SCL_PCLKT00-PadD2)") (class "Default")
      (node (ref "U1") (pin "D2") (pinfunction "PT12C_SCL_PCLKT00_D2") (pintype "bidirectional+no_connect"))
    )
    (net (code "54") (name "unconnected-(U1-PT12D_SDA_PCLKC00-PadC2)") (class "Default")
      (node (ref "U1") (pin "C2") (pinfunction "PT12D_SDA_PCLKC00_C2") (pintype "bidirectional+no_connect"))
    )
    (net (code "55") (name "unconnected-(U1-PT15C_JTAGENB-PadB2)") (class "Default")
      (node (ref "U1") (pin "B2") (pinfunction "PT15C_JTAGENB_B2") (pintype "bidirectional+no_connect"))
    )
    (net (code "56") (name "unconnected-(U1-PT15D_PROGRAMN-PadA2)") (class "Default")
      (node (ref "U1") (pin "A2") (pinfunction "PT15D_PROGRAMN_A2") (pintype "bidirectional+no_connect"))
    )
    (net (code "57") (name "unconnected-(U2-ADC_SDATA1{slash}CLKOUT{slash}MP6-Pad35)") (class "Default")
      (node (ref "U2") (pin "35") (pinfunction "ADC_SDATA1/CLKOUT/MP6_35") (pintype "bidirectional+no_connect"))
    )
    (net (code "58") (name "unconnected-(U2-DMIC0_1{slash}MP4-Pad37)") (class "Default")
      (node (ref "U2") (pin "37") (pinfunction "DMIC0_1/MP4_37") (pintype "bidirectional+no_connect"))
    )
    (net (code "59") (name "unconnected-(U2-DMIC2_3{slash}MP5-Pad36)") (class "Default")
      (node (ref "U2") (pin "36") (pinfunction "DMIC2_3/MP5_36") (pintype "bidirectional+no_connect"))
    )
    (net (code "60") (name "unconnected-(U2-HPOUTRN-Pad25)") (class "Default")
      (node (ref "U2") (pin "25") (pinfunction "HPOUTRN_25") (pintype "output+no_connect"))
    )
    (net (code "61") (name "unconnected-(U2-HPOUTRP-Pad26)") (class "Default")
      (node (ref "U2") (pin "26") (pinfunction "HPOUTRP_26") (pintype "output+no_connect"))
    )
    (net (code "62") (name "unconnected-(U2-MICBIAS0-Pad6)") (class "Default")
      (node (ref "U2") (pin "6") (pinfunction "MICBIAS0_6") (pintype "power_in+no_connect"))
    )
    (net (code "63") (name "unconnected-(U2-MICBIAS1-Pad7)") (class "Default")
      (node (ref "U2") (pin "7") (pinfunction "MICBIAS1_7") (pintype "power_in+no_connect"))
    )
    (net (code "64") (name "unconnected-(U2-XTALO-Pad38)") (class "Default")
      (node (ref "U2") (pin "38") (pinfunction "XTALO_38") (pintype "output+no_connect"))
    )
    (net (code "65") (name "unconnected-(U3-ASCX-Pad3)") (class "Default")
      (node (ref "U3") (pin "3") (pinfunction "ASCX_3") (pintype "bidirectional+no_connect"))
    )
    (net (code "66") (name "unconnected-(U3-ASDX-Pad2)") (class "Default")
      (node (ref "U3") (pin "2") (pinfunction "ASDX_2") (pintype "bidirectional+no_connect"))
    )
    (net (code "67") (name "unconnected-(U3-INT1-Pad4)") (class "Default")
      (node (ref "U3") (pin "4") (pinfunction "INT1_4") (pintype "bidirectional+no_connect"))
    )
    (net (code "68") (name "unconnected-(U3-INT2-Pad9)") (class "Default")
      (node (ref "U3") (pin "9") (pinfunction "INT2_9") (pintype "bidirectional+no_connect"))
    )
    (net (code "69") (name "unconnected-(U3-OCSB-Pad10)") (class "Default")
      (node (ref "U3") (pin "10") (pinfunction "OCSB_10") (pintype "bidirectional+no_connect"))
    )
    (net (code "70") (name "unconnected-(U3-OSDO-Pad11)") (class "Default")
      (node (ref "U3") (pin "11") (pinfunction "OSDO_11") (pintype "bidirectional+no_connect"))
    )
    (net (code "71") (name "unconnected-(U4-NC-Pad5)") (class "Default")
      (node (ref "U4") (pin "5") (pinfunction "NC_5") (pintype "passive+no_connect"))
    )
    (net (code "72") (name "unconnected-(U4-NC-Pad6)") (class "Default")
      (node (ref "U4") (pin "6") (pinfunction "NC_6") (pintype "passive+no_connect"))
    )
  )
)
